# node1-esp32s3-waveshare.net
KiCad netlist of a schematic drawn in EasyEDA
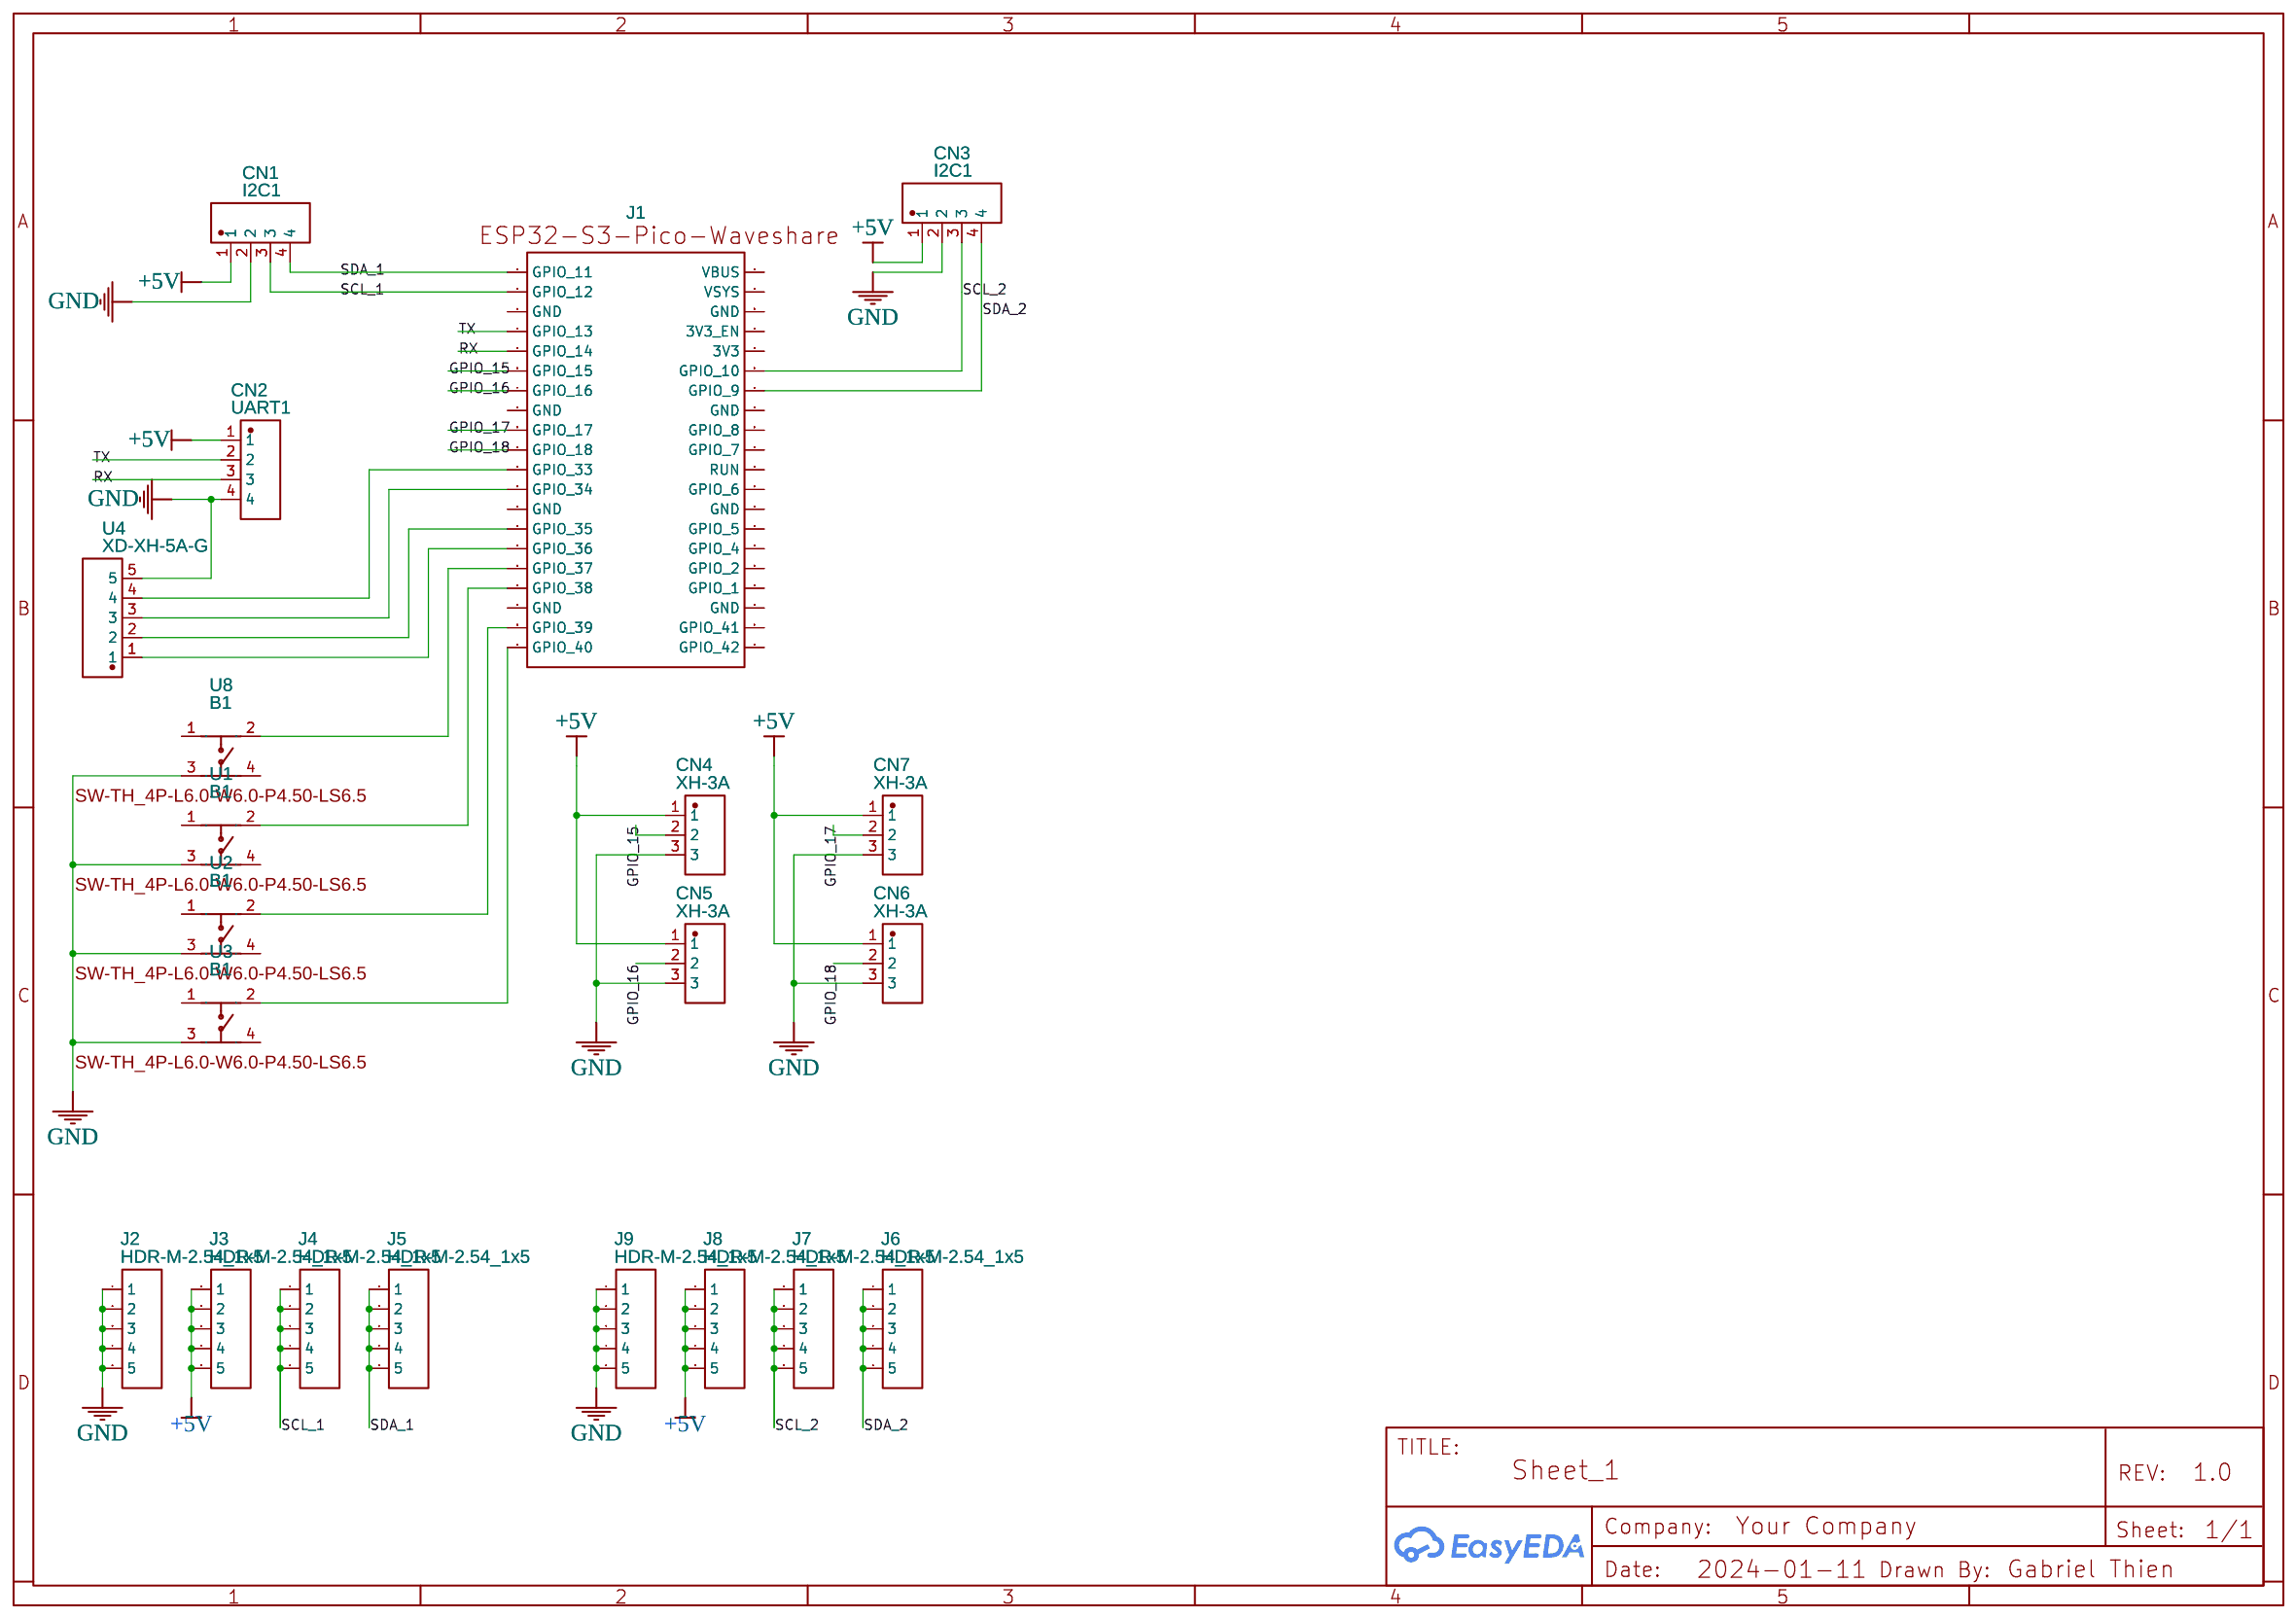
[diagram p0: schematic sheet]

(export (version "E")
  (design (tool "Eeschema 10.0.6"))
  (components
    (comp (ref "CN1")
      (value "I2C1")
      (fields (field (name "Manufacturer Part") "Header 4"))
      (libsource (lib "") (part "HEADER 4"))
    )
    (comp (ref "CN2")
      (value "UART1")
      (fields (field (name "Manufacturer Part") "Header 4"))
      (libsource (lib "") (part "HEADER 4_1"))
    )
    (comp (ref "CN3")
      (value "I2C1")
      (fields (field (name "Manufacturer Part") "Header 4"))
      (libsource (lib "") (part "HEADER 4"))
    )
    (comp (ref "CN4")
      (value "XH-3A")
      (fields (field (name "Manufacturer Part") "XH-3A 红色") (field (name "Manufacturer") "BOOMELE(博穆精密)"))
      (libsource (lib "") (part "XH-3A 红色"))
    )
    (comp (ref "CN5")
      (value "XH-3A")
      (fields (field (name "Manufacturer Part") "XH-3A 红色") (field (name "Manufacturer") "BOOMELE(博穆精密)"))
      (libsource (lib "") (part "XH-3A 红色"))
    )
    (comp (ref "CN6")
      (value "XH-3A")
      (fields (field (name "Manufacturer Part") "XH-3A 红色") (field (name "Manufacturer") "BOOMELE(博穆精密)"))
      (libsource (lib "") (part "XH-3A 红色"))
    )
    (comp (ref "CN7")
      (value "XH-3A")
      (fields (field (name "Manufacturer Part") "XH-3A 红色") (field (name "Manufacturer") "BOOMELE(博穆精密)"))
      (libsource (lib "") (part "XH-3A 红色"))
    )
    (comp (ref "J1")
      (value "ESP32-S3-Pico-Waveshare-Symbol")
      (fields (field (name "Manufacturer") "Waveshare"))
      (libsource (lib "") (part "ESP32-S3-Pico-Waveshare-Symbol"))
    )
    (comp (ref "J2") (value "HDR-M-2.54_1x5") (libsource (lib "") (part "HDR-M-2.54_1x5")))
    (comp (ref "J3") (value "HDR-M-2.54_1x5") (libsource (lib "") (part "HDR-M-2.54_1x5")))
    (comp (ref "J4") (value "HDR-M-2.54_1x5") (libsource (lib "") (part "HDR-M-2.54_1x5")))
    (comp (ref "J5") (value "HDR-M-2.54_1x5") (libsource (lib "") (part "HDR-M-2.54_1x5")))
    (comp (ref "J6") (value "HDR-M-2.54_1x5") (libsource (lib "") (part "HDR-M-2.54_1x5")))
    (comp (ref "J7") (value "HDR-M-2.54_1x5") (libsource (lib "") (part "HDR-M-2.54_1x5")))
    (comp (ref "J8") (value "HDR-M-2.54_1x5") (libsource (lib "") (part "HDR-M-2.54_1x5")))
    (comp (ref "J9") (value "HDR-M-2.54_1x5") (libsource (lib "") (part "HDR-M-2.54_1x5")))
    (comp (ref "U1")
      (value "B1")
      (fields (field (name "Manufacturer Part") "MJTP1230") (field (name "Manufacturer") "APEM"))
      (libsource (lib "") (part "MJTP1230"))
    )
    (comp (ref "U2")
      (value "B1")
      (fields (field (name "Manufacturer Part") "MJTP1230") (field (name "Manufacturer") "APEM"))
      (libsource (lib "") (part "MJTP1230"))
    )
    (comp (ref "U3")
      (value "B1")
      (fields (field (name "Manufacturer Part") "MJTP1230") (field (name "Manufacturer") "APEM"))
      (libsource (lib "") (part "MJTP1230"))
    )
    (comp (ref "U4")
      (value "XD-XH-5A-G")
      (fields (field (name "Manufacturer") "XUNDA(讯答)"))
      (libsource (lib "") (part "XD-XH-5A-G"))
    )
    (comp (ref "U8")
      (value "B1")
      (fields (field (name "Manufacturer Part") "MJTP1230") (field (name "Manufacturer") "APEM"))
      (libsource (lib "") (part "MJTP1230"))
    )
  )
  (nets
    (net (code "1") (name "+5V") (class "Default")
      (node (ref "CN1") (pin "1") (pinfunction "1_1") (pintype "unspecified"))
      (node (ref "CN2") (pin "1") (pinfunction "1_1") (pintype "unspecified"))
      (node (ref "CN3") (pin "1") (pinfunction "1_1") (pintype "unspecified"))
      (node (ref "CN4") (pin "1") (pinfunction "1_1") (pintype "unspecified"))
      (node (ref "CN5") (pin "1") (pinfunction "1_1") (pintype "unspecified"))
      (node (ref "CN6") (pin "1") (pinfunction "1_1") (pintype "unspecified"))
      (node (ref "CN7") (pin "1") (pinfunction "1_1") (pintype "unspecified"))
      (node (ref "J3") (pin "1") (pinfunction "1_1") (pintype "unspecified"))
      (node (ref "J3") (pin "2") (pinfunction "2_2") (pintype "unspecified"))
      (node (ref "J3") (pin "3") (pinfunction "3_3") (pintype "unspecified"))
      (node (ref "J3") (pin "4") (pinfunction "4_4") (pintype "unspecified"))
      (node (ref "J3") (pin "5") (pinfunction "5_5") (pintype "unspecified"))
      (node (ref "J8") (pin "1") (pinfunction "1_1") (pintype "unspecified"))
      (node (ref "J8") (pin "2") (pinfunction "2_2") (pintype "unspecified"))
      (node (ref "J8") (pin "3") (pinfunction "3_3") (pintype "unspecified"))
      (node (ref "J8") (pin "4") (pinfunction "4_4") (pintype "unspecified"))
      (node (ref "J8") (pin "5") (pinfunction "5_5") (pintype "unspecified"))
    )
    (net (code "2") (name "/GPIO_15") (class "Default")
      (node (ref "CN4") (pin "2") (pinfunction "2_2") (pintype "unspecified"))
      (node (ref "J1") (pin "6") (pinfunction "GPIO_15_6") (pintype "unspecified"))
    )
    (net (code "3") (name "/GPIO_16") (class "Default")
      (node (ref "CN5") (pin "2") (pinfunction "2_2") (pintype "unspecified"))
      (node (ref "J1") (pin "7") (pinfunction "GPIO_16_7") (pintype "unspecified"))
    )
    (net (code "4") (name "/GPIO_17") (class "Default")
      (node (ref "CN7") (pin "2") (pinfunction "2_2") (pintype "unspecified"))
      (node (ref "J1") (pin "9") (pinfunction "GPIO_17_9") (pintype "unspecified"))
    )
    (net (code "5") (name "/GPIO_18") (class "Default")
      (node (ref "CN6") (pin "2") (pinfunction "2_2") (pintype "unspecified"))
      (node (ref "J1") (pin "10") (pinfunction "GPIO_18_10") (pintype "unspecified"))
    )
    (net (code "6") (name "/RX") (class "Default")
      (node (ref "CN2") (pin "3") (pinfunction "3_3") (pintype "unspecified"))
      (node (ref "J1") (pin "5") (pinfunction "GPIO_14_5") (pintype "unspecified"))
    )
    (net (code "7") (name "/SCL_1") (class "Default")
      (node (ref "CN1") (pin "3") (pinfunction "3_3") (pintype "unspecified"))
      (node (ref "J1") (pin "2") (pinfunction "GPIO_12_2") (pintype "unspecified"))
      (node (ref "J4") (pin "1") (pinfunction "1_1") (pintype "unspecified"))
      (node (ref "J4") (pin "2") (pinfunction "2_2") (pintype "unspecified"))
      (node (ref "J4") (pin "3") (pinfunction "3_3") (pintype "unspecified"))
      (node (ref "J4") (pin "4") (pinfunction "4_4") (pintype "unspecified"))
      (node (ref "J4") (pin "5") (pinfunction "5_5") (pintype "unspecified"))
    )
    (net (code "8") (name "/SCL_2") (class "Default")
      (node (ref "CN3") (pin "3") (pinfunction "3_3") (pintype "unspecified"))
      (node (ref "J1") (pin "35") (pinfunction "GPIO_10_35") (pintype "unspecified"))
      (node (ref "J7") (pin "1") (pinfunction "1_1") (pintype "unspecified"))
      (node (ref "J7") (pin "2") (pinfunction "2_2") (pintype "unspecified"))
      (node (ref "J7") (pin "3") (pinfunction "3_3") (pintype "unspecified"))
      (node (ref "J7") (pin "4") (pinfunction "4_4") (pintype "unspecified"))
      (node (ref "J7") (pin "5") (pinfunction "5_5") (pintype "unspecified"))
    )
    (net (code "9") (name "/SDA_1") (class "Default")
      (node (ref "CN1") (pin "4") (pinfunction "4_4") (pintype "unspecified"))
      (node (ref "J1") (pin "1") (pinfunction "GPIO_11_1") (pintype "unspecified"))
      (node (ref "J5") (pin "1") (pinfunction "1_1") (pintype "unspecified"))
      (node (ref "J5") (pin "2") (pinfunction "2_2") (pintype "unspecified"))
      (node (ref "J5") (pin "3") (pinfunction "3_3") (pintype "unspecified"))
      (node (ref "J5") (pin "4") (pinfunction "4_4") (pintype "unspecified"))
      (node (ref "J5") (pin "5") (pinfunction "5_5") (pintype "unspecified"))
    )
    (net (code "10") (name "/SDA_2") (class "Default")
      (node (ref "CN3") (pin "4") (pinfunction "4_4") (pintype "unspecified"))
      (node (ref "J1") (pin "34") (pinfunction "GPIO_9_34") (pintype "unspecified"))
      (node (ref "J6") (pin "1") (pinfunction "1_1") (pintype "unspecified"))
      (node (ref "J6") (pin "2") (pinfunction "2_2") (pintype "unspecified"))
      (node (ref "J6") (pin "3") (pinfunction "3_3") (pintype "unspecified"))
      (node (ref "J6") (pin "4") (pinfunction "4_4") (pintype "unspecified"))
      (node (ref "J6") (pin "5") (pinfunction "5_5") (pintype "unspecified"))
    )
    (net (code "11") (name "/TX") (class "Default")
      (node (ref "CN2") (pin "2") (pinfunction "2_2") (pintype "unspecified"))
      (node (ref "J1") (pin "4") (pinfunction "GPIO_13_4") (pintype "unspecified"))
    )
    (net (code "12") (name "GND") (class "Default")
      (node (ref "CN1") (pin "2") (pinfunction "2_2") (pintype "unspecified"))
      (node (ref "CN2") (pin "4") (pinfunction "4_4") (pintype "unspecified"))
      (node (ref "CN3") (pin "2") (pinfunction "2_2") (pintype "unspecified"))
      (node (ref "CN4") (pin "3") (pinfunction "3_3") (pintype "unspecified"))
      (node (ref "CN5") (pin "3") (pinfunction "3_3") (pintype "unspecified"))
      (node (ref "CN6") (pin "3") (pinfunction "3_3") (pintype "unspecified"))
      (node (ref "CN7") (pin "3") (pinfunction "3_3") (pintype "unspecified"))
      (node (ref "J2") (pin "1") (pinfunction "1_1") (pintype "unspecified"))
      (node (ref "J2") (pin "2") (pinfunction "2_2") (pintype "unspecified"))
      (node (ref "J2") (pin "3") (pinfunction "3_3") (pintype "unspecified"))
      (node (ref "J2") (pin "4") (pinfunction "4_4") (pintype "unspecified"))
      (node (ref "J2") (pin "5") (pinfunction "5_5") (pintype "unspecified"))
      (node (ref "J9") (pin "1") (pinfunction "1_1") (pintype "unspecified"))
      (node (ref "J9") (pin "2") (pinfunction "2_2") (pintype "unspecified"))
      (node (ref "J9") (pin "3") (pinfunction "3_3") (pintype "unspecified"))
      (node (ref "J9") (pin "4") (pinfunction "4_4") (pintype "unspecified"))
      (node (ref "J9") (pin "5") (pinfunction "5_5") (pintype "unspecified"))
      (node (ref "U1") (pin "3") (pinfunction "3_3") (pintype "unspecified"))
      (node (ref "U2") (pin "3") (pinfunction "3_3") (pintype "unspecified"))
      (node (ref "U3") (pin "3") (pinfunction "3_3") (pintype "unspecified"))
      (node (ref "U4") (pin "5") (pinfunction "5_5") (pintype "unspecified"))
      (node (ref "U8") (pin "3") (pinfunction "3_3") (pintype "unspecified"))
    )
    (net (code "13") (name "Net-(J1-GPIO_33)") (class "Default")
      (node (ref "J1") (pin "11") (pinfunction "GPIO_33_11") (pintype "unspecified"))
      (node (ref "U4") (pin "4") (pinfunction "4_4") (pintype "unspecified"))
    )
    (net (code "14") (name "Net-(J1-GPIO_34)") (class "Default")
      (node (ref "J1") (pin "12") (pinfunction "GPIO_34_12") (pintype "unspecified"))
      (node (ref "U4") (pin "3") (pinfunction "3_3") (pintype "unspecified"))
    )
    (net (code "15") (name "Net-(J1-GPIO_35)") (class "Default")
      (node (ref "J1") (pin "14") (pinfunction "GPIO_35_14") (pintype "unspecified"))
      (node (ref "U4") (pin "2") (pinfunction "2_2") (pintype "unspecified"))
    )
    (net (code "16") (name "Net-(J1-GPIO_36)") (class "Default")
      (node (ref "J1") (pin "15") (pinfunction "GPIO_36_15") (pintype "unspecified"))
      (node (ref "U4") (pin "1") (pinfunction "1_1") (pintype "unspecified"))
    )
    (net (code "17") (name "Net-(J1-GPIO_37)") (class "Default")
      (node (ref "J1") (pin "16") (pinfunction "GPIO_37_16") (pintype "unspecified"))
      (node (ref "U8") (pin "2") (pinfunction "2_2") (pintype "unspecified"))
    )
    (net (code "18") (name "Net-(J1-GPIO_38)") (class "Default")
      (node (ref "J1") (pin "17") (pinfunction "GPIO_38_17") (pintype "unspecified"))
      (node (ref "U1") (pin "2") (pinfunction "2_2") (pintype "unspecified"))
    )
    (net (code "19") (name "Net-(J1-GPIO_39)") (class "Default")
      (node (ref "J1") (pin "19") (pinfunction "GPIO_39_19") (pintype "unspecified"))
      (node (ref "U2") (pin "2") (pinfunction "2_2") (pintype "unspecified"))
    )
    (net (code "20") (name "Net-(J1-GPIO_40)") (class "Default")
      (node (ref "J1") (pin "20") (pinfunction "GPIO_40_20") (pintype "unspecified"))
      (node (ref "U3") (pin "2") (pinfunction "2_2") (pintype "unspecified"))
    )
    (net (code "21") (name "unconnected-(J1-3V3-Pad36)") (class "Default")
      (node (ref "J1") (pin "36") (pinfunction "3V3_36") (pintype "unspecified"))
    )
    (net (code "22") (name "unconnected-(J1-3V3_EN-Pad37)") (class "Default")
      (node (ref "J1") (pin "37") (pinfunction "3V3_EN_37") (pintype "unspecified"))
    )
    (net (code "23") (name "unconnected-(J1-GND-Pad3)") (class "Default")
      (node (ref "J1") (pin "3") (pinfunction "GND_3") (pintype "unspecified"))
    )
    (net (code "24") (name "unconnected-(J1-GND-Pad8)") (class "Default")
      (node (ref "J1") (pin "8") (pinfunction "GND_8") (pintype "unspecified"))
    )
    (net (code "25") (name "unconnected-(J1-GND-Pad13)") (class "Default")
      (node (ref "J1") (pin "13") (pinfunction "GND_13") (pintype "unspecified"))
    )
    (net (code "26") (name "unconnected-(J1-GND-Pad18)") (class "Default")
      (node (ref "J1") (pin "18") (pinfunction "GND_18") (pintype "unspecified"))
    )
    (net (code "27") (name "unconnected-(J1-GND-Pad23)") (class "Default")
      (node (ref "J1") (pin "23") (pinfunction "GND_23") (pintype "unspecified"))
    )
    (net (code "28") (name "unconnected-(J1-GND-Pad28)") (class "Default")
      (node (ref "J1") (pin "28") (pinfunction "GND_28") (pintype "unspecified"))
    )
    (net (code "29") (name "unconnected-(J1-GND-Pad33)") (class "Default")
      (node (ref "J1") (pin "33") (pinfunction "GND_33") (pintype "unspecified"))
    )
    (net (code "30") (name "unconnected-(J1-GND-Pad38)") (class "Default")
      (node (ref "J1") (pin "38") (pinfunction "GND_38") (pintype "unspecified"))
    )
    (net (code "31") (name "unconnected-(J1-GPIO_1-Pad24)") (class "Default")
      (node (ref "J1") (pin "24") (pinfunction "GPIO_1_24") (pintype "unspecified"))
    )
    (net (code "32") (name "unconnected-(J1-GPIO_2-Pad25)") (class "Default")
      (node (ref "J1") (pin "25") (pinfunction "GPIO_2_25") (pintype "unspecified"))
    )
    (net (code "33") (name "unconnected-(J1-GPIO_4-Pad26)") (class "Default")
      (node (ref "J1") (pin "26") (pinfunction "GPIO_4_26") (pintype "unspecified"))
    )
    (net (code "34") (name "unconnected-(J1-GPIO_5-Pad27)") (class "Default")
      (node (ref "J1") (pin "27") (pinfunction "GPIO_5_27") (pintype "unspecified"))
    )
    (net (code "35") (name "unconnected-(J1-GPIO_6-Pad29)") (class "Default")
      (node (ref "J1") (pin "29") (pinfunction "GPIO_6_29") (pintype "unspecified"))
    )
    (net (code "36") (name "unconnected-(J1-GPIO_7-Pad31)") (class "Default")
      (node (ref "J1") (pin "31") (pinfunction "GPIO_7_31") (pintype "unspecified"))
    )
    (net (code "37") (name "unconnected-(J1-GPIO_8-Pad32)") (class "Default")
      (node (ref "J1") (pin "32") (pinfunction "GPIO_8_32") (pintype "unspecified"))
    )
    (net (code "38") (name "unconnected-(J1-GPIO_41-Pad22)") (class "Default")
      (node (ref "J1") (pin "22") (pinfunction "GPIO_41_22") (pintype "unspecified"))
    )
    (net (code "39") (name "unconnected-(J1-GPIO_42-Pad21)") (class "Default")
      (node (ref "J1") (pin "21") (pinfunction "GPIO_42_21") (pintype "unspecified"))
    )
    (net (code "40") (name "unconnected-(J1-RUN-Pad30)") (class "Default")
      (node (ref "J1") (pin "30") (pinfunction "RUN_30") (pintype "unspecified"))
    )
    (net (code "41") (name "unconnected-(J1-VBUS-Pad40)") (class "Default")
      (node (ref "J1") (pin "40") (pinfunction "VBUS_40") (pintype "unspecified"))
    )
    (net (code "42") (name "unconnected-(J1-VSYS-Pad39)") (class "Default")
      (node (ref "J1") (pin "39") (pinfunction "VSYS_39") (pintype "unspecified"))
    )
    (net (code "43") (name "unconnected-(U1-Pad1)") (class "Default")
      (node (ref "U1") (pin "1") (pinfunction "1_1") (pintype "unspecified"))
    )
    (net (code "44") (name "unconnected-(U1-Pad4)") (class "Default")
      (node (ref "U1") (pin "4") (pinfunction "4_4") (pintype "unspecified"))
    )
    (net (code "45") (name "unconnected-(U2-Pad1)") (class "Default")
      (node (ref "U2") (pin "1") (pinfunction "1_1") (pintype "unspecified"))
    )
    (net (code "46") (name "unconnected-(U2-Pad4)") (class "Default")
      (node (ref "U2") (pin "4") (pinfunction "4_4") (pintype "unspecified"))
    )
    (net (code "47") (name "unconnected-(U3-Pad1)") (class "Default")
      (node (ref "U3") (pin "1") (pinfunction "1_1") (pintype "unspecified"))
    )
    (net (code "48") (name "unconnected-(U3-Pad4)") (class "Default")
      (node (ref "U3") (pin "4") (pinfunction "4_4") (pintype "unspecified"))
    )
    (net (code "49") (name "unconnected-(U8-Pad1)") (class "Default")
      (node (ref "U8") (pin "1") (pinfunction "1_1") (pintype "unspecified"))
    )
    (net (code "50") (name "unconnected-(U8-Pad4)") (class "Default")
      (node (ref "U8") (pin "4") (pinfunction "4_4") (pintype "unspecified"))
    )
  )
)
